# FMC_connector_AB.net
KiCad netlist of a schematic drawn in Altium Designer
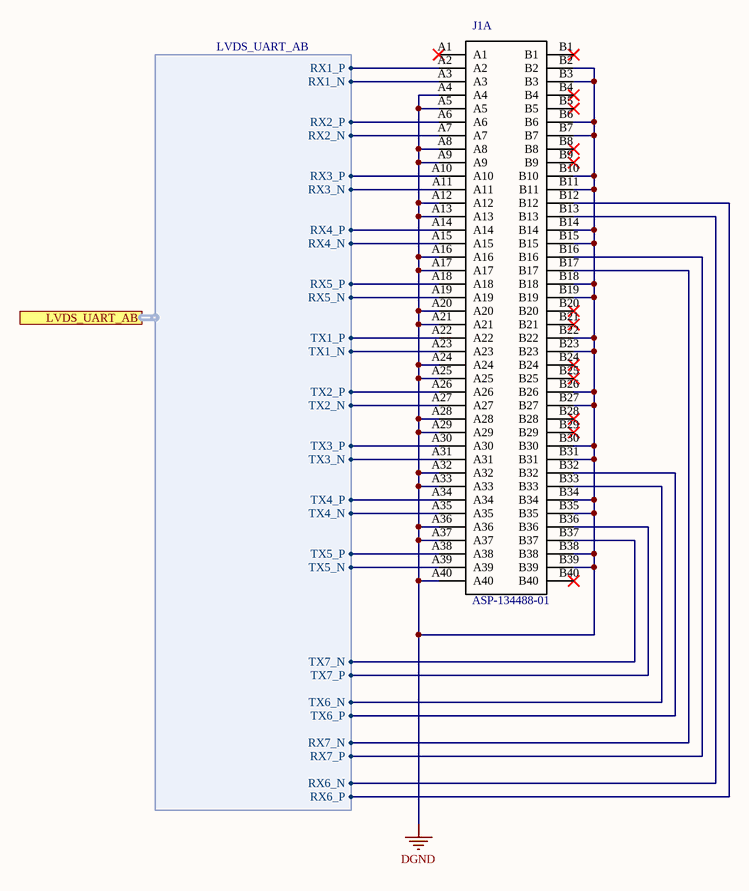
[diagram p0: FMC_connector_AB.SchDoc]

(export (version "E")
  (design (tool "Eeschema 10.0.6"))
  (components
    (comp (ref "J1")
      (value "ASP-134488-01")
      (footprint "*SAMTEC_ASP-134488-01_ASP-134488-01(Primary)")
      (libsource (lib "Components") (part "ASP-134488-01"))
    )
  )
  (nets
    (net (code "2") (name "/RX1_N") (class "Default")
      (node (ref "J1") (pin "A3") (pinfunction "A3_A3") (pintype "passive"))
    )
    (net (code "3") (name "/RX1_P") (class "Default")
      (node (ref "J1") (pin "A2") (pinfunction "A2_A2") (pintype "passive"))
    )
    (net (code "4") (name "/RX2_N") (class "Default")
      (node (ref "J1") (pin "A7") (pinfunction "A7_A7") (pintype "passive"))
    )
    (net (code "5") (name "/RX2_P") (class "Default")
      (node (ref "J1") (pin "A6") (pinfunction "A6_A6") (pintype "passive"))
    )
    (net (code "6") (name "/RX3_N") (class "Default")
      (node (ref "J1") (pin "A11") (pinfunction "A11_A11") (pintype "passive"))
    )
    (net (code "7") (name "/RX3_P") (class "Default")
      (node (ref "J1") (pin "A10") (pinfunction "A10_A10") (pintype "passive"))
    )
    (net (code "8") (name "/RX4_N") (class "Default")
      (node (ref "J1") (pin "A15") (pinfunction "A15_A15") (pintype "passive"))
    )
    (net (code "9") (name "/RX4_P") (class "Default")
      (node (ref "J1") (pin "A14") (pinfunction "A14_A14") (pintype "passive"))
    )
    (net (code "10") (name "/RX5_N") (class "Default")
      (node (ref "J1") (pin "A19") (pinfunction "A19_A19") (pintype "passive"))
    )
    (net (code "11") (name "/RX5_P") (class "Default")
      (node (ref "J1") (pin "A18") (pinfunction "A18_A18") (pintype "passive"))
    )
    (net (code "12") (name "/RX6_N") (class "Default")
      (node (ref "J1") (pin "B13") (pinfunction "B13_B13") (pintype "passive"))
    )
    (net (code "13") (name "/RX6_P") (class "Default")
      (node (ref "J1") (pin "B12") (pinfunction "B12_B12") (pintype "passive"))
    )
    (net (code "14") (name "/RX7_N") (class "Default")
      (node (ref "J1") (pin "B17") (pinfunction "B17_B17") (pintype "passive"))
    )
    (net (code "15") (name "/RX7_P") (class "Default")
      (node (ref "J1") (pin "B16") (pinfunction "B16_B16") (pintype "passive"))
    )
    (net (code "16") (name "/TX1_N") (class "Default")
      (node (ref "J1") (pin "A23") (pinfunction "A23_A23") (pintype "passive"))
    )
    (net (code "17") (name "/TX1_P") (class "Default")
      (node (ref "J1") (pin "A22") (pinfunction "A22_A22") (pintype "passive"))
    )
    (net (code "18") (name "/TX2_N") (class "Default")
      (node (ref "J1") (pin "A27") (pinfunction "A27_A27") (pintype "passive"))
    )
    (net (code "19") (name "/TX2_P") (class "Default")
      (node (ref "J1") (pin "A26") (pinfunction "A26_A26") (pintype "passive"))
    )
    (net (code "20") (name "/TX3_N") (class "Default")
      (node (ref "J1") (pin "A31") (pinfunction "A31_A31") (pintype "passive"))
    )
    (net (code "21") (name "/TX3_P") (class "Default")
      (node (ref "J1") (pin "A30") (pinfunction "A30_A30") (pintype "passive"))
    )
    (net (code "22") (name "/TX4_N") (class "Default")
      (node (ref "J1") (pin "A35") (pinfunction "A35_A35") (pintype "passive"))
    )
    (net (code "23") (name "/TX4_P") (class "Default")
      (node (ref "J1") (pin "A34") (pinfunction "A34_A34") (pintype "passive"))
    )
    (net (code "24") (name "/TX5_N") (class "Default")
      (node (ref "J1") (pin "A39") (pinfunction "A39_A39") (pintype "passive"))
    )
    (net (code "25") (name "/TX5_P") (class "Default")
      (node (ref "J1") (pin "A38") (pinfunction "A38_A38") (pintype "passive"))
    )
    (net (code "26") (name "/TX6_N") (class "Default")
      (node (ref "J1") (pin "B33") (pinfunction "B33_B33") (pintype "passive"))
    )
    (net (code "27") (name "/TX6_P") (class "Default")
      (node (ref "J1") (pin "B32") (pinfunction "B32_B32") (pintype "passive"))
    )
    (net (code "28") (name "/TX7_N") (class "Default")
      (node (ref "J1") (pin "B37") (pinfunction "B37_B37") (pintype "passive"))
    )
    (net (code "29") (name "/TX7_P") (class "Default")
      (node (ref "J1") (pin "B36") (pinfunction "B36_B36") (pintype "passive"))
    )
    (net (code "31") (name "DGND") (class "Default")
      (node (ref "J1") (pin "A12") (pinfunction "A12_A12") (pintype "passive"))
      (node (ref "J1") (pin "A13") (pinfunction "A13_A13") (pintype "passive"))
      (node (ref "J1") (pin "A16") (pinfunction "A16_A16") (pintype "passive"))
      (node (ref "J1") (pin "A17") (pinfunction "A17_A17") (pintype "passive"))
      (node (ref "J1") (pin "A20") (pinfunction "A20_A20") (pintype "passive"))
      (node (ref "J1") (pin "A21") (pinfunction "A21_A21") (pintype "passive"))
      (node (ref "J1") (pin "A24") (pinfunction "A24_A24") (pintype "passive"))
      (node (ref "J1") (pin "A25") (pinfunction "A25_A25") (pintype "passive"))
      (node (ref "J1") (pin "A28") (pinfunction "A28_A28") (pintype "passive"))
      (node (ref "J1") (pin "A29") (pinfunction "A29_A29") (pintype "passive"))
      (node (ref "J1") (pin "A32") (pinfunction "A32_A32") (pintype "passive"))
      (node (ref "J1") (pin "A33") (pinfunction "A33_A33") (pintype "passive"))
      (node (ref "J1") (pin "A36") (pinfunction "A36_A36") (pintype "passive"))
      (node (ref "J1") (pin "A37") (pinfunction "A37_A37") (pintype "passive"))
      (node (ref "J1") (pin "A4") (pinfunction "A4_A4") (pintype "passive"))
      (node (ref "J1") (pin "A40") (pinfunction "A40_A40") (pintype "passive"))
      (node (ref "J1") (pin "A5") (pinfunction "A5_A5") (pintype "passive"))
      (node (ref "J1") (pin "A8") (pinfunction "A8_A8") (pintype "passive"))
      (node (ref "J1") (pin "A9") (pinfunction "A9_A9") (pintype "passive"))
      (node (ref "J1") (pin "B10") (pinfunction "B10_B10") (pintype "passive"))
      (node (ref "J1") (pin "B11") (pinfunction "B11_B11") (pintype "passive"))
      (node (ref "J1") (pin "B14") (pinfunction "B14_B14") (pintype "passive"))
      (node (ref "J1") (pin "B15") (pinfunction "B15_B15") (pintype "passive"))
      (node (ref "J1") (pin "B18") (pinfunction "B18_B18") (pintype "passive"))
      (node (ref "J1") (pin "B19") (pinfunction "B19_B19") (pintype "passive"))
      (node (ref "J1") (pin "B2") (pinfunction "B2_B2") (pintype "passive"))
      (node (ref "J1") (pin "B22") (pinfunction "B22_B22") (pintype "passive"))
      (node (ref "J1") (pin "B23") (pinfunction "B23_B23") (pintype "passive"))
      (node (ref "J1") (pin "B26") (pinfunction "B26_B26") (pintype "passive"))
      (node (ref "J1") (pin "B27") (pinfunction "B27_B27") (pintype "passive"))
      (node (ref "J1") (pin "B3") (pinfunction "B3_B3") (pintype "passive"))
      (node (ref "J1") (pin "B30") (pinfunction "B30_B30") (pintype "passive"))
      (node (ref "J1") (pin "B31") (pinfunction "B31_B31") (pintype "passive"))
      (node (ref "J1") (pin "B34") (pinfunction "B34_B34") (pintype "passive"))
      (node (ref "J1") (pin "B35") (pinfunction "B35_B35") (pintype "passive"))
      (node (ref "J1") (pin "B38") (pinfunction "B38_B38") (pintype "passive"))
      (node (ref "J1") (pin "B39") (pinfunction "B39_B39") (pintype "passive"))
      (node (ref "J1") (pin "B6") (pinfunction "B6_B6") (pintype "passive"))
      (node (ref "J1") (pin "B7") (pinfunction "B7_B7") (pintype "passive"))
    )
    (net (code "32") (name "unconnected-(J1-PadA1)") (class "Default")
      (node (ref "J1") (pin "A1") (pinfunction "A1_A1") (pintype "passive+no_connect"))
    )
    (net (code "33") (name "unconnected-(J1-PadB1)") (class "Default")
      (node (ref "J1") (pin "B1") (pinfunction "B1_B1") (pintype "passive+no_connect"))
    )
    (net (code "34") (name "unconnected-(J1-PadB4)") (class "Default")
      (node (ref "J1") (pin "B4") (pinfunction "B4_B4") (pintype "passive+no_connect"))
    )
    (net (code "35") (name "unconnected-(J1-PadB5)") (class "Default")
      (node (ref "J1") (pin "B5") (pinfunction "B5_B5") (pintype "passive+no_connect"))
    )
    (net (code "36") (name "unconnected-(J1-PadB8)") (class "Default")
      (node (ref "J1") (pin "B8") (pinfunction "B8_B8") (pintype "passive+no_connect"))
    )
    (net (code "37") (name "unconnected-(J1-PadB9)") (class "Default")
      (node (ref "J1") (pin "B9") (pinfunction "B9_B9") (pintype "passive+no_connect"))
    )
    (net (code "38") (name "unconnected-(J1-PadB20)") (class "Default")
      (node (ref "J1") (pin "B20") (pinfunction "B20_B20") (pintype "passive+no_connect"))
    )
    (net (code "39") (name "unconnected-(J1-PadB21)") (class "Default")
      (node (ref "J1") (pin "B21") (pinfunction "B21_B21") (pintype "passive+no_connect"))
    )
    (net (code "40") (name "unconnected-(J1-PadB24)") (class "Default")
      (node (ref "J1") (pin "B24") (pinfunction "B24_B24") (pintype "passive+no_connect"))
    )
    (net (code "41") (name "unconnected-(J1-PadB25)") (class "Default")
      (node (ref "J1") (pin "B25") (pinfunction "B25_B25") (pintype "passive+no_connect"))
    )
    (net (code "42") (name "unconnected-(J1-PadB28)") (class "Default")
      (node (ref "J1") (pin "B28") (pinfunction "B28_B28") (pintype "passive+no_connect"))
    )
    (net (code "43") (name "unconnected-(J1-PadB29)") (class "Default")
      (node (ref "J1") (pin "B29") (pinfunction "B29_B29") (pintype "passive+no_connect"))
    )
    (net (code "44") (name "unconnected-(J1-PadB40)") (class "Default")
      (node (ref "J1") (pin "B40") (pinfunction "B40_B40") (pintype "passive+no_connect"))
    )
  )
)
